# v2.net
KiCad netlist of a schematic drawn in EAGLE
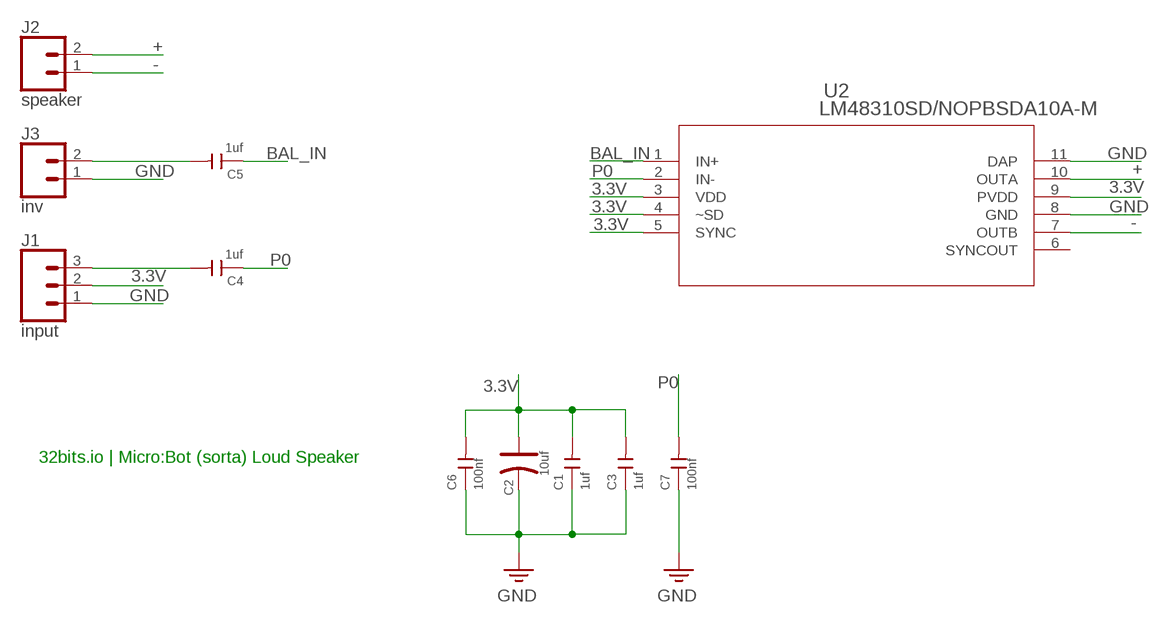
[diagram p0: schematic, sheet 1]

(export (version "E")
  (design (tool "Eeschema 10.0.6"))
  (components
    (comp (ref "C1")
      (value "1uf")
      (footprint "eagle-import:C0603")
      (fields (field (name "MPN") "CC0603KRX7R8BB105"))
      (libsource (lib "eagle-import") (part "CERAMIC-1UF-25V-10%-X7R(0603)"))
    )
    (comp (ref "C2")
      (value "10uf")
      (footprint "eagle-import:PC-D5.3MM")
      (fields (field (name "MPN") "KS 100uF/16V"))
      (libsource (lib "eagle-import") (part "DIP-ALUMINUM-47UF-16V(D5-H7MM)"))
    )
    (comp (ref "C3")
      (value "1uf")
      (footprint "eagle-import:C0603")
      (fields (field (name "MPN") "CC0603KRX7R8BB105"))
      (libsource (lib "eagle-import") (part "CERAMIC-1UF-25V-10%-X7R(0603)"))
    )
    (comp (ref "C4")
      (value "1uf")
      (footprint "eagle-import:C0603")
      (fields (field (name "MPN") "CC0603KRX7R8BB105"))
      (libsource (lib "eagle-import") (part "CERAMIC-1UF-25V-10%-X7R(0603)"))
    )
    (comp (ref "C5")
      (value "1uf")
      (footprint "eagle-import:C0603")
      (fields (field (name "MPN") "CC0603KRX7R8BB105"))
      (libsource (lib "eagle-import") (part "CERAMIC-1UF-25V-10%-X7R(0603)"))
    )
    (comp (ref "C6")
      (value "100nf")
      (footprint "eagle-import:C0603")
      (fields (field (name "MPN") "CC0603KRX7R9BB104"))
      (libsource (lib "eagle-import") (part "CERAMIC-100NF-50V-10%-X7R(0603)"))
    )
    (comp (ref "C7")
      (value "100nf")
      (footprint "eagle-import:C0603")
      (fields (field (name "MPN") "CC0603KRX7R9BB104"))
      (libsource (lib "eagle-import") (part "CERAMIC-100NF-50V-10%-X7R(0603)"))
    )
    (comp (ref "J1")
      (value "input")
      (footprint "eagle-import:1X03_SMD_RA_MALE")
      (libsource (lib "eagle-import") (part "CONN_03SMD_RA_MALE"))
    )
    (comp (ref "J2")
      (value "speaker")
      (footprint "eagle-import:1X02")
      (libsource (lib "eagle-import") (part "CONN_02"))
    )
    (comp (ref "J3")
      (value "inv")
      (footprint "eagle-import:1X02")
      (libsource (lib "eagle-import") (part "CONN_02"))
    )
    (comp (ref "U2")
      (value "LM48310SD/NOPBSDA10A-M")
      (footprint "eagle-import:SDA10A-M")
      (fields (field (name "MANUFACTURER_PART_NUMBER") "LM48310SDNOPB"))
      (libsource (lib "eagle-import") (part "LM48310SD/NOPBSDA10A-M"))
    )
  )
  (nets
    (net (code "1") (name "/+") (class "Default")
      (node (ref "J2") (pin "2") (pinfunction "2_2") (pintype "passive"))
      (node (ref "U2") (pin "10") (pinfunction "OUTA_10") (pintype "output"))
    )
    (net (code "2") (name "/-") (class "Default")
      (node (ref "J2") (pin "1") (pinfunction "1_1") (pintype "passive"))
      (node (ref "U2") (pin "7") (pinfunction "OUTB_7") (pintype "output"))
    )
    (net (code "3") (name "/3.3V") (class "Default")
      (node (ref "C1") (pin "2") (pinfunction "2_2") (pintype "passive"))
      (node (ref "C2") (pin "+") (pinfunction "+_+") (pintype "passive"))
      (node (ref "C3") (pin "2") (pinfunction "2_2") (pintype "passive"))
      (node (ref "C6") (pin "2") (pinfunction "2_2") (pintype "passive"))
      (node (ref "J1") (pin "2") (pinfunction "2_2") (pintype "passive"))
      (node (ref "U2") (pin "3") (pinfunction "VDD_3") (pintype "power_in"))
      (node (ref "U2") (pin "4") (pinfunction "~{SD}_4") (pintype "input"))
      (node (ref "U2") (pin "5") (pinfunction "SYNC_5") (pintype "input"))
      (node (ref "U2") (pin "9") (pinfunction "PVDD_9") (pintype "power_in"))
    )
    (net (code "4") (name "/BAL_IN") (class "Default")
      (node (ref "C5") (pin "1") (pinfunction "1_1") (pintype "passive"))
      (node (ref "U2") (pin "1") (pinfunction "IN+_1") (pintype "input"))
    )
    (net (code "5") (name "/P0") (class "Default")
      (node (ref "C4") (pin "1") (pinfunction "1_1") (pintype "passive"))
      (node (ref "C7") (pin "2") (pinfunction "2_2") (pintype "passive"))
      (node (ref "U2") (pin "2") (pinfunction "IN-_2") (pintype "input"))
    )
    (net (code "6") (name "GND") (class "Default")
      (node (ref "C1") (pin "1") (pinfunction "1_1") (pintype "passive"))
      (node (ref "C2") (pin "-") (pinfunction "-_-") (pintype "passive"))
      (node (ref "C3") (pin "1") (pinfunction "1_1") (pintype "passive"))
      (node (ref "C6") (pin "1") (pinfunction "1_1") (pintype "passive"))
      (node (ref "C7") (pin "1") (pinfunction "1_1") (pintype "passive"))
      (node (ref "J1") (pin "1") (pinfunction "1_1") (pintype "passive"))
      (node (ref "J3") (pin "1") (pinfunction "1_1") (pintype "passive"))
      (node (ref "U2") (pin "11") (pinfunction "DAP_11") (pintype "power_in"))
      (node (ref "U2") (pin "8") (pinfunction "GND_8") (pintype "power_in"))
    )
    (net (code "7") (name "Net-(C4-Pad2)") (class "Default")
      (node (ref "C4") (pin "2") (pinfunction "2_2") (pintype "passive"))
      (node (ref "J1") (pin "3") (pinfunction "3_3") (pintype "passive"))
    )
    (net (code "8") (name "Net-(C5-Pad2)") (class "Default")
      (node (ref "C5") (pin "2") (pinfunction "2_2") (pintype "passive"))
      (node (ref "J3") (pin "2") (pinfunction "2_2") (pintype "passive"))
    )
    (net (code "9") (name "unconnected-(U2-SYNCOUT-Pad6)") (class "Default")
      (node (ref "U2") (pin "6") (pinfunction "SYNCOUT_6") (pintype "output"))
    )
  )
)
